# uC_Environment.net
KiCad netlist of a schematic drawn in Altium Designer
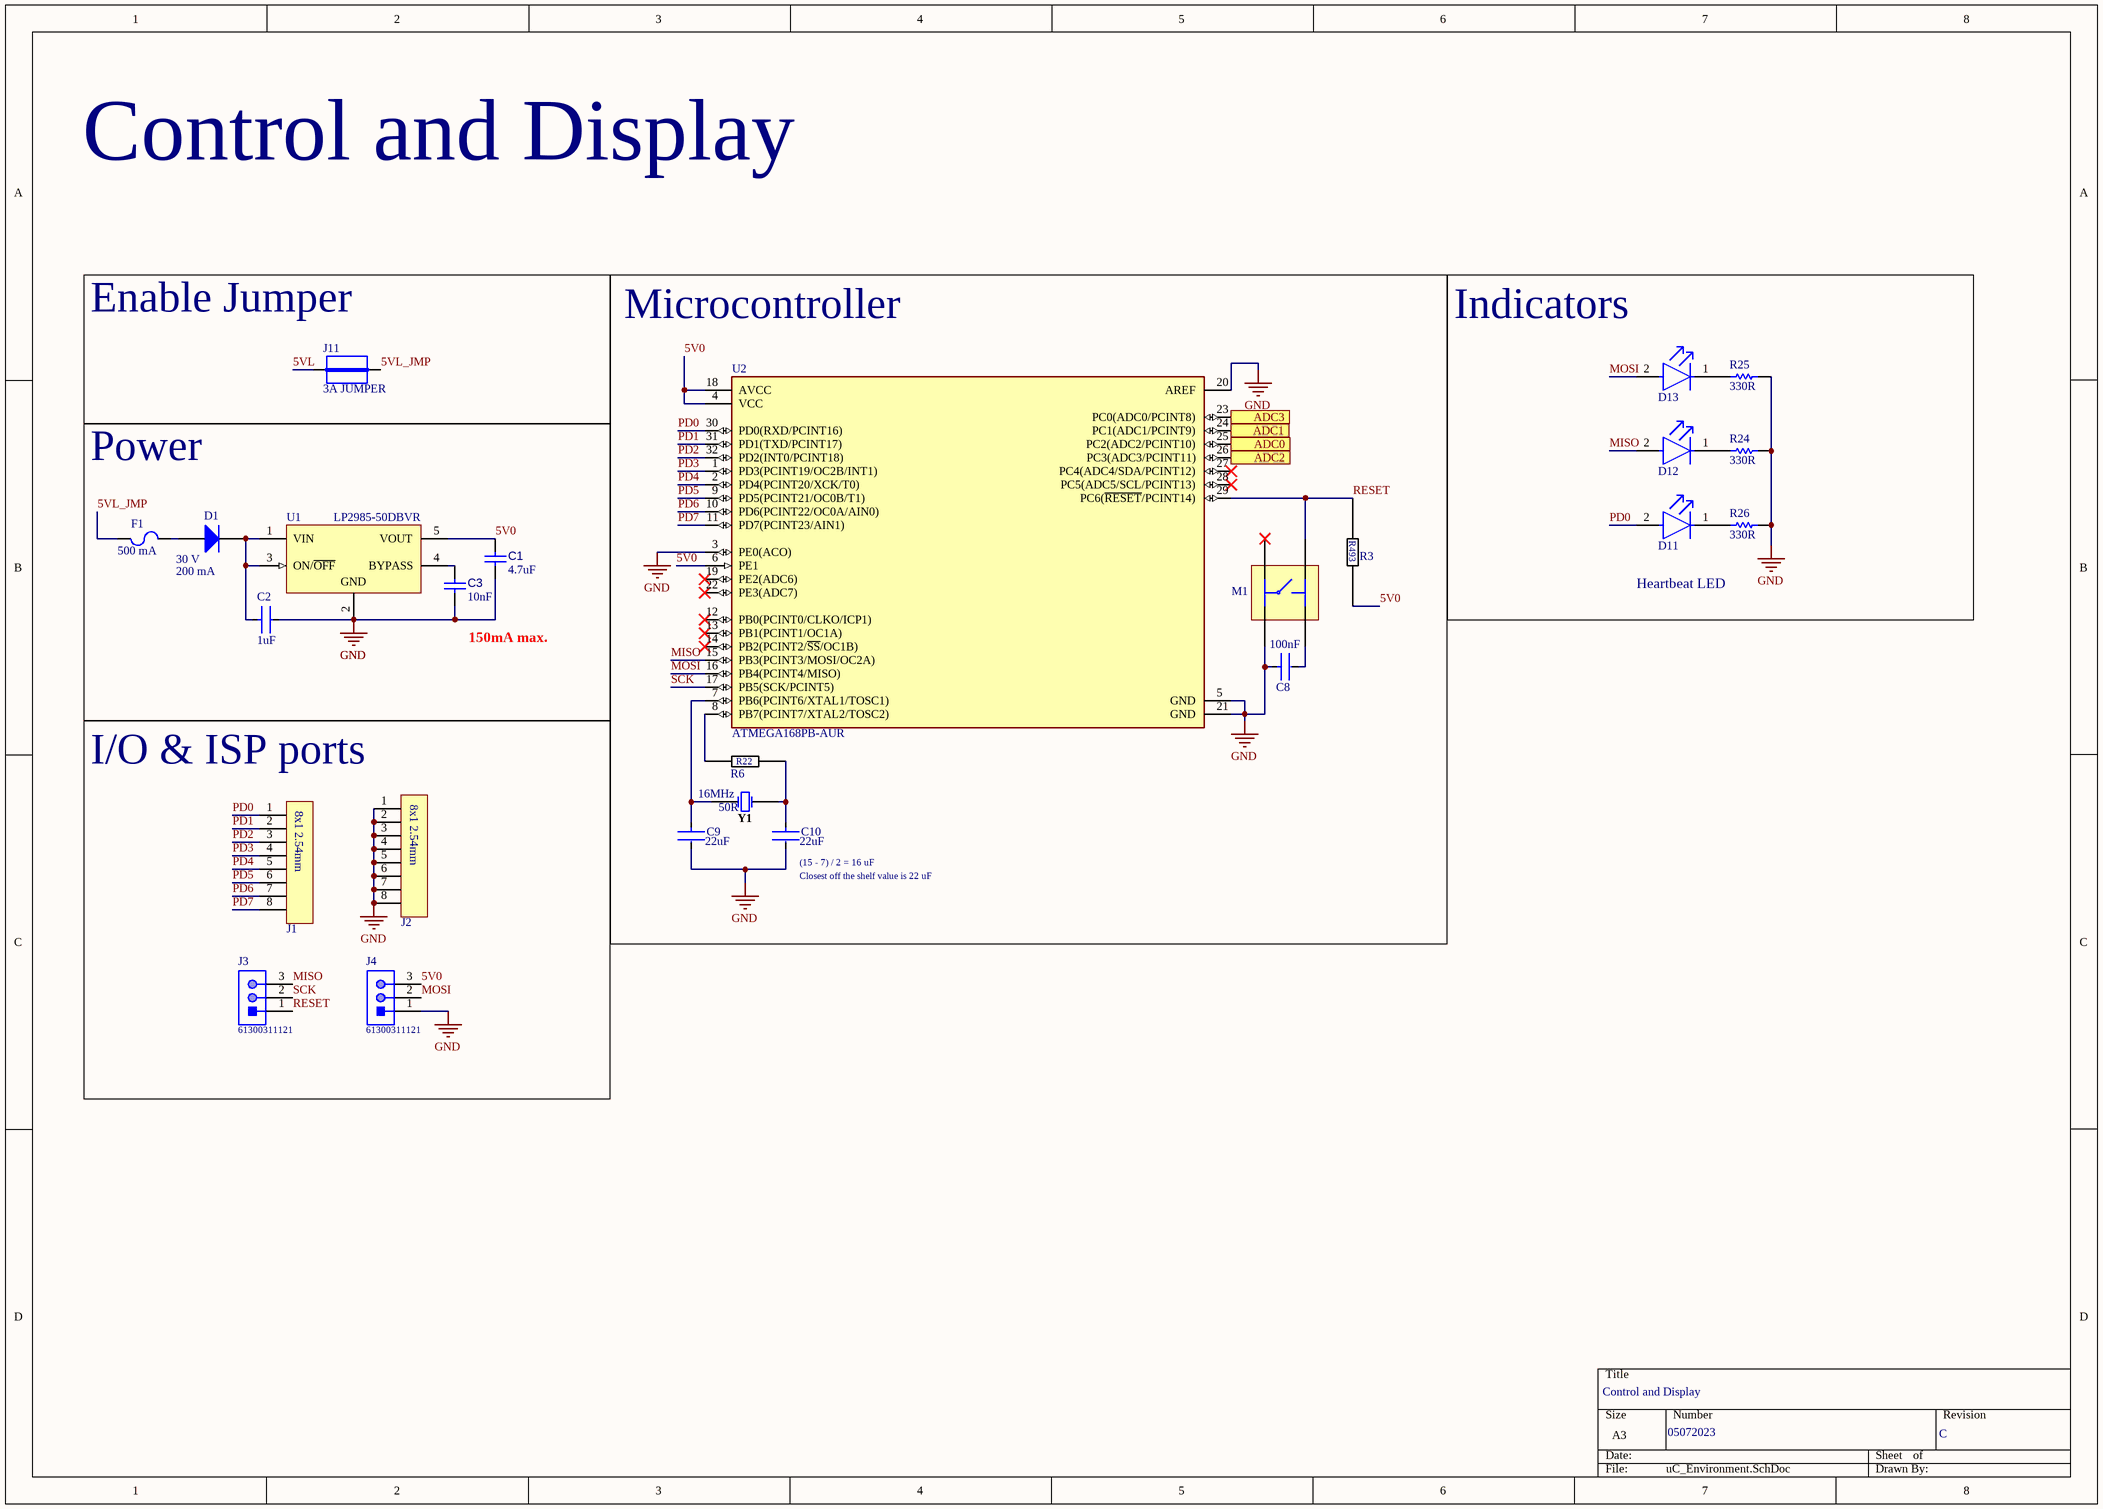
[diagram p0: uC_Environment.SchDoc]

(export (version "E")
  (design (tool "Eeschema 10.0.6"))
  (components
    (comp (ref "C1")
      (value "4.7uF")
      (footprint "CAPC3216X18N")
      (description "Ceramic capacitor SMD 1206 - 4700nF/25V, +-10%, X7R, Samsung, RoHS")
      (fields (field (name "Comment") "CL31B475KAHNNNE"))
      (libsource (lib "Cetys University") (part "CAP-NP-2"))
    )
    (comp (ref "C2")
      (value "CL10B105KA8NNNC")
      (footprint "FP-CL10-IPC_C")
      (description "CAP CER 1UF 25V X7R 0603")
      (fields
        (field (name "TOLERANCE") "10%")
        (field (name "CAPACITANCE") "1uF")
        (field (name "VOLTAGE") "25V")
      )
      (libsource (lib "Altium Content Vault") (part "11868f565c42a9108669ba33697ecf6"))
    )
    (comp (ref "C3")
      (value "10nF")
      (footprint "CAPC2012X08N")
      (description "Cap Ceramic 0.01uF 25V X7R 10% SMD 0805 125°C Paper T/R")
      (fields (field (name "Comment") "CL21B103KAANNNC"))
      (libsource (lib "Cetys University") (part "CAP-NP-2"))
    )
    (comp (ref "C8")
      (value "CL21B104KBCNNNC")
      (footprint "FP-CL21-IPC_C")
      (description "CL21 Series 0805 100nF 50V ±10% Tolerance X7R Multilayer Ceramic Chip Capacitor")
      (fields
        (field (name "TOLERANCE") "10%")
        (field (name "CAPACITANCE") "100nF")
        (field (name "VOLTAGE") "50V")
      )
      (libsource (lib "Altium Content Vault") (part "b4654b650e69147ec39a6b967a45e02"))
    )
    (comp (ref "C9")
      (value "C2012X5R1V226M125AC")
      (footprint "FP-C2012-125-0_2-MFG")
      (description "Multilayer Ceramic Capacitors 22μF ±20% 35V X5R SMD 0805")
      (fields (field (name "TOLERANCE") "20%") (field (name "CAPACITANCE") "22uF"))
      (libsource (lib "Altium Content Vault") (part "b4654b650e69147ec39a6b967a45e02"))
    )
    (comp (ref "C10")
      (value "C2012X5R1V226M125AC")
      (footprint "FP-C2012-125-0_2-MFG")
      (description "Multilayer Ceramic Capacitors 22μF ±20% 35V X5R SMD 0805")
      (fields (field (name "TOLERANCE") "20%") (field (name "CAPACITANCE") "22uF"))
      (libsource (lib "Altium Content Vault") (part "b4654b650e69147ec39a6b967a45e02"))
    )
    (comp (ref "D1")
      (value "RB521S30T1G")
      (footprint "ONSC-SOD-523-2-502-01_V")
      (description "Schottky Barrier Diode, 2-Pin SOD-523, Pb-Free, Tape and Reel")
      (fields
        (field (name "MANUFACTURER") "On Semiconductor")
        (field (name "PARAMETER 1") "30 V")
        (field (name "PARAMETER 2") "200 mA")
      )
      (libsource (lib "Altium Content Vault") (part "ONSC-D-K1A2-2"))
    )
    (comp (ref "D11")
      (value "LTST-C191TBKT")
      (footprint "FP-LTST-C191TBKT-MFG")
      (description "LED BLUE CLEAR CHIP SMD")
      (libsource (lib "Altium Content Vault") (part "8706943c75ba83719d021d2fdc84c58"))
    )
    (comp (ref "D12")
      (value "LTST-C191TBKT")
      (footprint "FP-LTST-C191TBKT-MFG")
      (description "LED BLUE CLEAR CHIP SMD")
      (libsource (lib "Altium Content Vault") (part "8706943c75ba83719d021d2fdc84c58"))
    )
    (comp (ref "D13")
      (value "LTST-C191TBKT")
      (footprint "FP-LTST-C191TBKT-MFG")
      (description "LED BLUE CLEAR CHIP SMD")
      (libsource (lib "Altium Content Vault") (part "8706943c75ba83719d021d2fdc84c58"))
    )
    (comp (ref "F1")
      (value "0ZCJ0050AF2E")
      (footprint "0ZCJ0050AF2E-Footprint-1")
      (fields (field (name "PARAMETER 1") "500 mA"))
      (libsource (lib "Cetys University") (part "0ZCJ0050AF2E-Symbol-1"))
    )
    (comp (ref "J1")
      (value "M22-2010805")
      (footprint "M22-2010805-Footprint-1")
      (description "Connector, Header, 8Pos, 1Row, 2Mm Rohs Compliant: Yes")
      (libsource (lib "Cetys University") (part "M22-2010805-Symbol-1"))
    )
    (comp (ref "J2")
      (value "M22-2010805")
      (footprint "M22-2010805-Footprint-1")
      (description "Connector, Header, 8Pos, 1Row, 2Mm Rohs Compliant: Yes")
      (libsource (lib "Cetys University") (part "M22-2010805-Symbol-1"))
    )
    (comp (ref "J3")
      (value "61300311121")
      (footprint "61300311121")
      (description "THT Vertical Pin Header WR-PHD, Pitch 2.54 mm, Single Row, 3 pins")
      (fields (field (name "MANUFACTURER") "Wurth Elektronik") (field (name "PUBLISHER") "WurthElektronik"))
      (libsource (lib "Altium Content Vault") (part "WE-CN-1P-M-R3"))
    )
    (comp (ref "J4")
      (value "61300311121")
      (footprint "61300311121")
      (description "THT Vertical Pin Header WR-PHD, Pitch 2.54 mm, Single Row, 3 pins")
      (fields (field (name "MANUFACTURER") "Wurth Elektronik") (field (name "PUBLISHER") "WurthElektronik"))
      (libsource (lib "Altium Content Vault") (part "WE-CN-1P-M-R3"))
    )
    (comp (ref "J11")
      (value "3A JUMPER")
      (footprint "3A JUMPER-Footprint-1")
      (libsource (lib "Cetys University") (part "JUMPER"))
    )
    (comp (ref "M1")
      (value "PTS815SJK250SMTRLFS")
      (footprint "PTS815SJK250SMTRLFS-Footprint-1")
      (description "Switch Tactile N.O. SPST Button J-Bend 0.05A 12VDC 2.45N SMD T/R")
      (libsource (lib "Cetys University") (part "PTS815SJK250SMTRLFS-Symbol-1"))
    )
    (comp (ref "R3")
      (value "RC0805FR-074K99L")
      (footprint "RESC2012X06N")
      (description "Res Thick Film 0805 4.99K Ohm 1% 0.125W(1/8W) ±100ppm/C Epoxy Pad SMD T/R")
      (libsource (lib "Cetys University") (part "RC0805FR-074K99L-Symbol-1"))
    )
    (comp (ref "R6")
      (value "RC0805JR-0722RL")
      (footprint "RESC2012X06N")
      (description "Res Thick Film 0805 22 Ohm 5% 0.125W(1/8W) ±100ppm/C Pad SMD T/R")
      (libsource (lib "Cetys University") (part "RC0805JR-0722RL"))
    )
    (comp (ref "R24")
      (value "ERJ-3EKF3300V")
      (footprint "RESC1608X55X30LL15T15")
      (description "Chip Resistor, 330 Ohm, +/- 1%, 0.1 W, -55 to 155 degC, 0603 (1608 Metric), RoHS, Tape and Reel")
      (fields (field (name "RESISTANCE") "330R"))
      (libsource (lib "Altium Content Vault") (part "RES-2"))
    )
    (comp (ref "R25")
      (value "ERJ-3EKF3300V")
      (footprint "RESC1608X55X30LL15T15")
      (description "Chip Resistor, 330 Ohm, +/- 1%, 0.1 W, -55 to 155 degC, 0603 (1608 Metric), RoHS, Tape and Reel")
      (fields (field (name "RESISTANCE") "330R"))
      (libsource (lib "Altium Content Vault") (part "RES-2"))
    )
    (comp (ref "R26")
      (value "ERJ-3EKF3300V")
      (footprint "RESC1608X55X30LL15T15")
      (description "Chip Resistor, 330 Ohm, +/- 1%, 0.1 W, -55 to 155 degC, 0603 (1608 Metric), RoHS, Tape and Reel")
      (fields (field (name "RESISTANCE") "330R"))
      (libsource (lib "Altium Content Vault") (part "RES-2"))
    )
    (comp (ref "U1")
      (value "LP2985-50DBVR")
      (footprint "DBV0005A_M")
      (fields (field (name "MANUFACTURER") "Texas Instruments"))
      (libsource (lib "Altium Content Vault") (part "TI-LP2985_A-10DBV5"))
    )
    (comp (ref "U2")
      (value "ATMEGA168PB-AUR")
      (footprint "FP-32A-MFG")
      (description "IC MCU 8BIT 16KB FLASH 32TQFP")
      (libsource (lib "Altium Content Vault") (part "5fb3611904dc3d2736123649c3553cc"))
    )
    (comp (ref "Y1")
      (value "ECS-160-20-3X-EN-TR")
      (footprint "ECS-160-20-3X-EN-TR-Footprint-1")
      (description "Crystal 16MHz ±30ppm (Tol) ±50ppm (Stability) 20pF FUND 50Ohm 2-Pin HC-49/USX SMD T/R")
      (fields (field (name "FREQUENCY") "16MHz") (field (name "ESR (EQUIVALENT SERIES RESISTANCE)") "50R"))
      (libsource (lib "Cetys University") (part "XTAL-2"))
    )
  )
  (nets
    (net (code "1") (name "/5V0") (class "Default")
      (node (ref "C1") (pin "1") (pinfunction "1_1") (pintype "passive"))
      (node (ref "J4") (pin "3") (pinfunction "3_3") (pintype "passive"))
      (node (ref "R3") (pin "2") (pinfunction "2_2") (pintype "passive"))
      (node (ref "U1") (pin "5") (pinfunction "VOUT_5") (pintype "power_in"))
      (node (ref "U2") (pin "18") (pinfunction "AVCC_18") (pintype "power_in"))
      (node (ref "U2") (pin "4") (pinfunction "VCC_4") (pintype "power_in"))
      (node (ref "U2") (pin "6") (pinfunction "PE1_6") (pintype "input"))
    )
    (net (code "2") (name "/5VL") (class "Default")
      (node (ref "J11") (pin "1") (pinfunction "1_1") (pintype "passive"))
    )
    (net (code "3") (name "/5VL_JMP") (class "Default")
      (node (ref "F1") (pin "1") (pinfunction "IN_1") (pintype "passive"))
      (node (ref "J11") (pin "2") (pinfunction "2_2") (pintype "passive"))
    )
    (net (code "4") (name "/ADC0") (class "Default")
      (node (ref "U2") (pin "25") (pinfunction "PC2(ADC2/PCINT10)_25") (pintype "bidirectional"))
    )
    (net (code "5") (name "/ADC1") (class "Default")
      (node (ref "U2") (pin "24") (pinfunction "PC1(ADC1/PCINT9)_24") (pintype "bidirectional"))
    )
    (net (code "6") (name "/ADC2") (class "Default")
      (node (ref "U2") (pin "26") (pinfunction "PC3(ADC3/PCINT11)_26") (pintype "bidirectional"))
    )
    (net (code "7") (name "/ADC3") (class "Default")
      (node (ref "U2") (pin "23") (pinfunction "PC0(ADC0/PCINT8)_23") (pintype "bidirectional"))
    )
    (net (code "8") (name "/MISO") (class "Default")
      (node (ref "D12") (pin "2") (pinfunction "A_2") (pintype "passive"))
      (node (ref "J3") (pin "3") (pinfunction "3_3") (pintype "passive"))
      (node (ref "U2") (pin "15") (pinfunction "PB3(PCINT3/MOSI/OC2A)_15") (pintype "bidirectional"))
    )
    (net (code "9") (name "/MOSI") (class "Default")
      (node (ref "D13") (pin "2") (pinfunction "A_2") (pintype "passive"))
      (node (ref "J4") (pin "2") (pinfunction "2_2") (pintype "passive"))
      (node (ref "U2") (pin "16") (pinfunction "PB4(PCINT4/MISO)_16") (pintype "bidirectional"))
    )
    (net (code "10") (name "/PD0") (class "Default")
      (node (ref "D11") (pin "2") (pinfunction "A_2") (pintype "passive"))
      (node (ref "J1") (pin "1") (pinfunction "1_1") (pintype "passive"))
      (node (ref "U2") (pin "30") (pinfunction "PD0(RXD/PCINT16)_30") (pintype "bidirectional"))
    )
    (net (code "11") (name "/PD1") (class "Default")
      (node (ref "J1") (pin "2") (pinfunction "2_2") (pintype "passive"))
      (node (ref "U2") (pin "31") (pinfunction "PD1(TXD/PCINT17)_31") (pintype "bidirectional"))
    )
    (net (code "12") (name "/PD2") (class "Default")
      (node (ref "J1") (pin "3") (pinfunction "3_3") (pintype "passive"))
      (node (ref "U2") (pin "32") (pinfunction "PD2(INT0/PCINT18)_32") (pintype "bidirectional"))
    )
    (net (code "13") (name "/PD3") (class "Default")
      (node (ref "J1") (pin "4") (pinfunction "4_4") (pintype "passive"))
      (node (ref "U2") (pin "1") (pinfunction "PD3(PCINT19/OC2B/INT1)_1") (pintype "bidirectional"))
    )
    (net (code "14") (name "/PD4") (class "Default")
      (node (ref "J1") (pin "5") (pinfunction "5_5") (pintype "passive"))
      (node (ref "U2") (pin "2") (pinfunction "PD4(PCINT20/XCK/T0)_2") (pintype "bidirectional"))
    )
    (net (code "15") (name "/PD5") (class "Default")
      (node (ref "J1") (pin "6") (pinfunction "6_6") (pintype "passive"))
      (node (ref "U2") (pin "9") (pinfunction "PD5(PCINT21/OC0B/T1)_9") (pintype "bidirectional"))
    )
    (net (code "16") (name "/PD6") (class "Default")
      (node (ref "J1") (pin "7") (pinfunction "7_7") (pintype "passive"))
      (node (ref "U2") (pin "10") (pinfunction "PD6(PCINT22/OC0A/AIN0)_10") (pintype "bidirectional"))
    )
    (net (code "17") (name "/PD7") (class "Default")
      (node (ref "J1") (pin "8") (pinfunction "8_8") (pintype "passive"))
      (node (ref "U2") (pin "11") (pinfunction "PD7(PCINT23/AIN1)_11") (pintype "bidirectional"))
    )
    (net (code "18") (name "/RESET") (class "Default")
      (node (ref "J3") (pin "1") (pinfunction "1_1") (pintype "passive"))
      (node (ref "M1") (pin "3") (pinfunction "B2_3") (pintype "passive"))
      (node (ref "R3") (pin "1") (pinfunction "1_1") (pintype "passive"))
      (node (ref "U2") (pin "29") (pinfunction "PC6(~{RESET}/PCINT14)_29") (pintype "bidirectional"))
    )
    (net (code "19") (name "/SCK") (class "Default")
      (node (ref "J3") (pin "2") (pinfunction "2_2") (pintype "passive"))
      (node (ref "U2") (pin "17") (pinfunction "PB5(SCK/PCINT5)_17") (pintype "bidirectional"))
    )
    (net (code "20") (name "GND") (class "Default")
      (node (ref "C1") (pin "2") (pinfunction "2_2") (pintype "passive"))
      (node (ref "C10") (pin "2") (pinfunction "2_2") (pintype "passive"))
      (node (ref "C2") (pin "2") (pinfunction "2_2") (pintype "passive"))
      (node (ref "C3") (pin "1") (pinfunction "1_1") (pintype "passive"))
      (node (ref "C8") (pin "1") (pinfunction "1_1") (pintype "passive"))
      (node (ref "C9") (pin "2") (pinfunction "2_2") (pintype "passive"))
      (node (ref "J2") (pin "1") (pinfunction "1_1") (pintype "passive"))
      (node (ref "J2") (pin "2") (pinfunction "2_2") (pintype "passive"))
      (node (ref "J2") (pin "3") (pinfunction "3_3") (pintype "passive"))
      (node (ref "J2") (pin "4") (pinfunction "4_4") (pintype "passive"))
      (node (ref "J2") (pin "5") (pinfunction "5_5") (pintype "passive"))
      (node (ref "J2") (pin "6") (pinfunction "6_6") (pintype "passive"))
      (node (ref "J2") (pin "7") (pinfunction "7_7") (pintype "passive"))
      (node (ref "J2") (pin "8") (pinfunction "8_8") (pintype "passive"))
      (node (ref "J4") (pin "1") (pinfunction "1_1") (pintype "passive"))
      (node (ref "M1") (pin "0") (pinfunction "A1_0") (pintype "passive"))
      (node (ref "R24") (pin "1") (pinfunction "1_1") (pintype "passive"))
      (node (ref "R25") (pin "1") (pinfunction "1_1") (pintype "passive"))
      (node (ref "R26") (pin "1") (pinfunction "1_1") (pintype "passive"))
      (node (ref "U1") (pin "2") (pinfunction "GND_2") (pintype "power_in"))
      (node (ref "U2") (pin "20") (pinfunction "AREF_20") (pintype "power_in"))
      (node (ref "U2") (pin "21") (pinfunction "GND_21") (pintype "power_in"))
      (node (ref "U2") (pin "3") (pinfunction "PE0(ACO)_3") (pintype "bidirectional"))
      (node (ref "U2") (pin "5") (pinfunction "GND_5") (pintype "power_in"))
    )
    (net (code "21") (name "Net-(C10-Pad1)") (class "Default")
      (node (ref "C10") (pin "1") (pinfunction "1_1") (pintype "passive"))
      (node (ref "R6") (pin "2") (pinfunction "2_2") (pintype "passive"))
      (node (ref "Y1") (pin "1") (pinfunction "1_1") (pintype "passive"))
    )
    (net (code "22") (name "Net-(D1-A)") (class "Default")
      (node (ref "D1") (pin "2") (pinfunction "A_2") (pintype "passive"))
      (node (ref "F1") (pin "2") (pinfunction "OUT_2") (pintype "passive"))
    )
    (net (code "23") (name "Net-(D1-K)") (class "Default")
      (node (ref "C2") (pin "1") (pinfunction "1_1") (pintype "passive"))
      (node (ref "D1") (pin "1") (pinfunction "K_1") (pintype "passive"))
      (node (ref "U1") (pin "1") (pinfunction "VIN_1") (pintype "power_in"))
      (node (ref "U1") (pin "3") (pinfunction "ON/~{OFF}_3") (pintype "input"))
    )
    (net (code "24") (name "Net-(D11-C)") (class "Default")
      (node (ref "D11") (pin "1") (pinfunction "C_1") (pintype "passive"))
      (node (ref "R26") (pin "2") (pinfunction "2_2") (pintype "passive"))
    )
    (net (code "25") (name "Net-(D12-C)") (class "Default")
      (node (ref "D12") (pin "1") (pinfunction "C_1") (pintype "passive"))
      (node (ref "R24") (pin "2") (pinfunction "2_2") (pintype "passive"))
    )
    (net (code "26") (name "Net-(D13-C)") (class "Default")
      (node (ref "D13") (pin "1") (pinfunction "C_1") (pintype "passive"))
      (node (ref "R25") (pin "2") (pinfunction "2_2") (pintype "passive"))
    )
    (net (code "27") (name "Net-(M1-A2)") (class "Default")
      (node (ref "C8") (pin "2") (pinfunction "2_2") (pintype "passive"))
      (node (ref "M1") (pin "2") (pinfunction "A2_2") (pintype "passive"))
    )
    (net (code "28") (name "Net-(U1-BYPASS)") (class "Default")
      (node (ref "C3") (pin "2") (pinfunction "2_2") (pintype "passive"))
      (node (ref "U1") (pin "4") (pinfunction "BYPASS_4") (pintype "passive"))
    )
    (net (code "29") (name "Net-(U2-PB6(PCINT6{slash}XTAL1{slash}TOSC1))") (class "Default")
      (node (ref "C9") (pin "1") (pinfunction "1_1") (pintype "passive"))
      (node (ref "U2") (pin "7") (pinfunction "PB6(PCINT6/XTAL1/TOSC1)_7") (pintype "bidirectional"))
      (node (ref "Y1") (pin "2") (pinfunction "2_2") (pintype "passive"))
    )
    (net (code "30") (name "Net-(U2-PB7(PCINT7{slash}XTAL2{slash}TOSC2))") (class "Default")
      (node (ref "R6") (pin "1") (pinfunction "1_1") (pintype "passive"))
      (node (ref "U2") (pin "8") (pinfunction "PB7(PCINT7/XTAL2/TOSC2)_8") (pintype "bidirectional"))
    )
    (net (code "31") (name "unconnected-(M1-B1-Pad1)") (class "Default")
      (node (ref "M1") (pin "1") (pinfunction "B1_1") (pintype "passive+no_connect"))
    )
    (net (code "32") (name "unconnected-(U2-PB0(PCINT0{slash}CLKO{slash}ICP1)-Pad12)") (class "Default")
      (node (ref "U2") (pin "12") (pinfunction "PB0(PCINT0/CLKO/ICP1)_12") (pintype "bidirectional+no_connect"))
    )
    (net (code "33") (name "unconnected-(U2-PB1(PCINT1{slash}OC1A)-Pad13)") (class "Default")
      (node (ref "U2") (pin "13") (pinfunction "PB1(PCINT1/OC1A)_13") (pintype "bidirectional+no_connect"))
    )
    (net (code "34") (name "unconnected-(U2-PB2(PCINT2{slash}~{SS}{slash}OC1B)-Pad14)") (class "Default")
      (node (ref "U2") (pin "14") (pinfunction "PB2(PCINT2/~{SS}/OC1B)_14") (pintype "bidirectional+no_connect"))
    )
    (net (code "35") (name "unconnected-(U2-PC4(ADC4{slash}SDA{slash}PCINT12)-Pad27)") (class "Default")
      (node (ref "U2") (pin "27") (pinfunction "PC4(ADC4/SDA/PCINT12)_27") (pintype "bidirectional+no_connect"))
    )
    (net (code "36") (name "unconnected-(U2-PC5(ADC5{slash}SCL{slash}PCINT13)-Pad28)") (class "Default")
      (node (ref "U2") (pin "28") (pinfunction "PC5(ADC5/SCL/PCINT13)_28") (pintype "bidirectional+no_connect"))
    )
    (net (code "37") (name "unconnected-(U2-PE2(ADC6)-Pad19)") (class "Default")
      (node (ref "U2") (pin "19") (pinfunction "PE2(ADC6)_19") (pintype "bidirectional+no_connect"))
    )
    (net (code "38") (name "unconnected-(U2-PE3(ADC7)-Pad22)") (class "Default")
      (node (ref "U2") (pin "22") (pinfunction "PE3(ADC7)_22") (pintype "bidirectional+no_connect"))
    )
  )
)
